# BLACKPEARLROBOT.net
KiCad netlist of a schematic drawn in Altium Designer
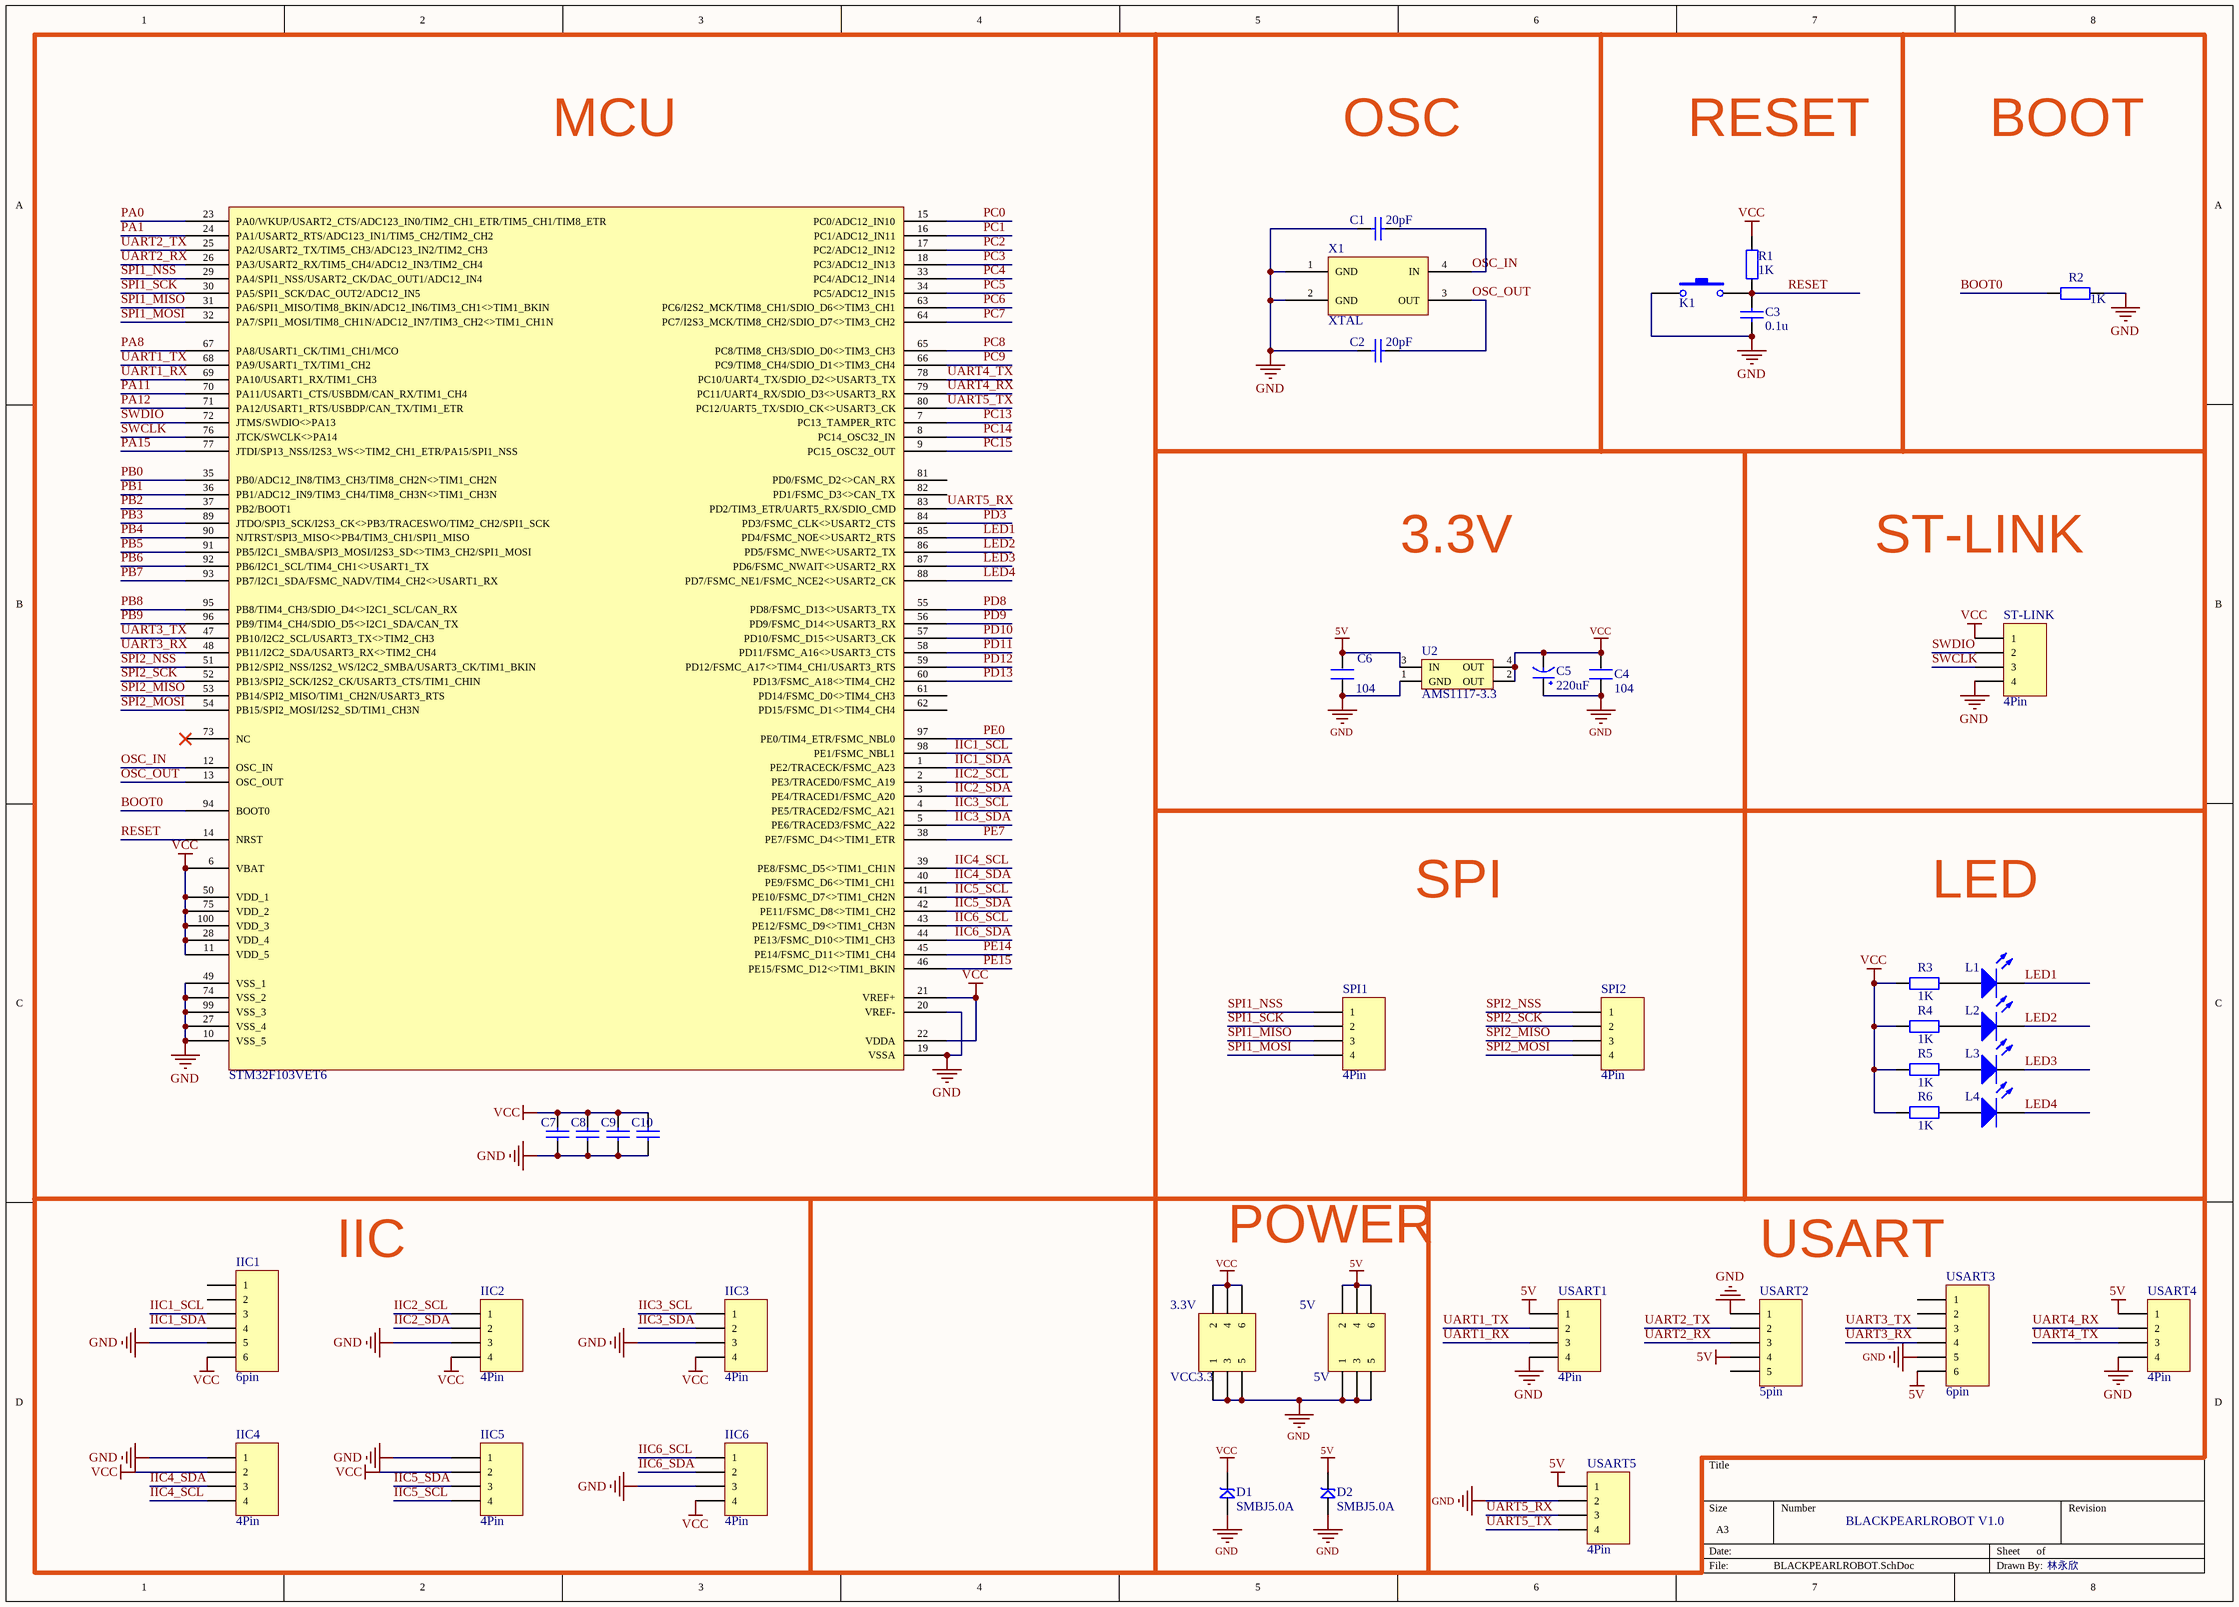
[diagram p0: BLACKPEARLROBOT.SchDoc]

(export (version "E")
  (design (tool "Eeschema 10.0.6"))
  (components
    (comp (ref "3.3V")
      (value "VCC3.3")
      (footprint "HDR2X3")
      (description "Header, 3-Pin, Dual row")
      (fields (field (name "PUBLISHER") "Altium Limited"))
      (libsource (lib "Explorer STM32F407封装库") (part "Header 3X2"))
    )
    (comp (ref "5V")
      (value "5V")
      (footprint "HDR2X3")
      (description "Header, 3-Pin, Dual row")
      (fields (field (name "PUBLISHER") "Altium Limited"))
      (libsource (lib "Explorer STM32F407封装库") (part "Header 3X2"))
    )
    (comp (ref "C1") (value "20pF") (footprint "Cap-0603") (libsource (lib "元件2") (part "Cap-0603")))
    (comp (ref "C2") (value "20pF") (footprint "Cap-0603") (libsource (lib "元件2") (part "Cap-0603")))
    (comp (ref "C3") (value "0.1u") (footprint "Cap-0603") (libsource (lib "元件2") (part "Cap-0603")))
    (comp (ref "C4") (value "104") (footprint "0603P") (libsource (lib "Explorer STM32F407封装库") (part "C")))
    (comp (ref "C5")
      (value "220uF")
      (footprint "CC6.56.5")
      (libsource (lib "Explorer STM32F407封装库") (part "CAP"))
    )
    (comp (ref "C6") (value "104") (footprint "0603P") (libsource (lib "Explorer STM32F407封装库") (part "C")))
    (comp (ref "C7") (value "0.1u") (footprint "Cap-0603") (libsource (lib "元件2") (part "Cap-0603")))
    (comp (ref "C8") (value "0.1u") (footprint "Cap-0603") (libsource (lib "元件2") (part "Cap-0603")))
    (comp (ref "C9") (value "0.1u") (footprint "Cap-0603") (libsource (lib "元件2") (part "Cap-0603")))
    (comp (ref "C10") (value "0.1u") (footprint "Cap-0603") (libsource (lib "元件2") (part "Cap-0603")))
    (comp (ref "D1")
      (value "SMBJ5.0A")
      (footprint "SMBJ")
      (description "TVS")
      (libsource (lib "Explorer STM32F407封装库") (part "SMBJ"))
    )
    (comp (ref "D2")
      (value "SMBJ5.0A")
      (footprint "SMBJ")
      (description "TVS")
      (libsource (lib "Explorer STM32F407封装库") (part "SMBJ"))
    )
    (comp (ref "IIC1")
      (value "6pin")
      (footprint "HDR1X6")
      (description "Header, 6-Pin")
      (fields (field (name "PUBLISHER") "Altium Limited"))
      (libsource (lib "Miscellaneous Connectors") (part "Header 6"))
    )
    (comp (ref "IIC2") (value "4Pin") (footprint "4Pin") (libsource (lib "元件2") (part "4Pin")))
    (comp (ref "IIC3") (value "4Pin") (footprint "4Pin") (libsource (lib "元件2") (part "4Pin")))
    (comp (ref "IIC4") (value "4Pin") (footprint "4Pin") (libsource (lib "元件2") (part "4Pin")))
    (comp (ref "IIC5") (value "4Pin") (footprint "4Pin") (libsource (lib "元件2") (part "4Pin")))
    (comp (ref "IIC6") (value "4Pin") (footprint "4Pin") (libsource (lib "元件2") (part "4Pin")))
    (comp (ref "K1") (value "KEY") (footprint "KEY-tie") (libsource (lib "元件2") (part "KEY-tie")))
    (comp (ref "L1") (value "LED-0805") (footprint "LED-0805") (libsource (lib "元件2") (part "LED-0805")))
    (comp (ref "L2") (value "LED-0805") (footprint "LED-0805") (libsource (lib "元件2") (part "LED-0805")))
    (comp (ref "L3") (value "LED-0805") (footprint "LED-0805") (libsource (lib "元件2") (part "LED-0805")))
    (comp (ref "L4") (value "LED-0805") (footprint "LED-0805") (libsource (lib "元件2") (part "LED-0805")))
    (comp (ref "R1") (value "1K") (footprint "RES-0603") (libsource (lib "元件2") (part "RST-0603")))
    (comp (ref "R2") (value "1K") (footprint "RES-0603") (libsource (lib "") (part "RST-0603_1")))
    (comp (ref "R3") (value "1K") (footprint "RES-0603") (libsource (lib "") (part "RST-0603_1")))
    (comp (ref "R4") (value "1K") (footprint "RES-0603") (libsource (lib "") (part "RST-0603_1")))
    (comp (ref "R5") (value "1K") (footprint "RES-0603") (libsource (lib "") (part "RST-0603_1")))
    (comp (ref "R6") (value "1K") (footprint "RES-0603") (libsource (lib "") (part "RST-0603_1")))
    (comp (ref "SPI1") (value "4Pin") (footprint "4Pin") (libsource (lib "元件2") (part "4Pin")))
    (comp (ref "SPI2") (value "4Pin") (footprint "4Pin") (libsource (lib "元件2") (part "4Pin")))
    (comp (ref "ST-LINK") (value "4Pin") (footprint "4Pin") (libsource (lib "元件2") (part "4Pin")))
    (comp (ref "U1")
      (value "STM32F103VET6")
      (footprint "STM32F103VET6")
      (libsource (lib "元件2") (part "STM32F103VET6"))
    )
    (comp (ref "U2")
      (value "AMS1117-3.3")
      (footprint "AMS1117")
      (libsource (lib "Explorer STM32F407封装库") (part "AMS1117"))
    )
    (comp (ref "USART1") (value "4Pin") (footprint "4Pin") (libsource (lib "元件2") (part "4Pin")))
    (comp (ref "USART2")
      (value "5pin")
      (footprint "HDR1X5")
      (description "Header, 5-Pin")
      (fields (field (name "PUBLISHER") "Altium Limited"))
      (libsource (lib "Miscellaneous Connectors") (part "Header 5"))
    )
    (comp (ref "USART3")
      (value "6pin")
      (footprint "HDR1X6")
      (description "Header, 6-Pin")
      (fields (field (name "PUBLISHER") "Altium Limited"))
      (libsource (lib "Miscellaneous Connectors") (part "Header 6"))
    )
    (comp (ref "USART4") (value "4Pin") (footprint "4Pin") (libsource (lib "元件2") (part "4Pin")))
    (comp (ref "USART5") (value "4Pin") (footprint "4Pin") (libsource (lib "元件2") (part "4Pin")))
    (comp (ref "X1") (value "XTAL") (footprint "XTAL-tie") (libsource (lib "元件2") (part "XTAL-tie")))
  )
  (nets
    (net (code "1") (name "/BOOT0") (class "Default")
      (node (ref "R2") (pin "1") (pinfunction "1_1") (pintype "passive"))
      (node (ref "U1") (pin "94") (pinfunction "BOOT0_94") (pintype "passive"))
    )
    (net (code "2") (name "/IIC1_SCL") (class "Default")
      (node (ref "IIC1") (pin "3") (pinfunction "3_3") (pintype "passive"))
      (node (ref "U1") (pin "98") (pinfunction "PE1/FSMC_NBL1_98") (pintype "passive"))
    )
    (net (code "3") (name "/IIC1_SDA") (class "Default")
      (node (ref "IIC1") (pin "4") (pinfunction "4_4") (pintype "passive"))
      (node (ref "U1") (pin "1") (pinfunction "PE2/TRACECK/FSMC_A23_1") (pintype "passive"))
    )
    (net (code "4") (name "/IIC2_SCL") (class "Default")
      (node (ref "IIC2") (pin "1") (pinfunction "1_1") (pintype "passive"))
      (node (ref "U1") (pin "2") (pinfunction "PE3/TRACED0/FSMC_A19_2") (pintype "passive"))
    )
    (net (code "5") (name "/IIC2_SDA") (class "Default")
      (node (ref "IIC2") (pin "2") (pinfunction "2_2") (pintype "passive"))
      (node (ref "U1") (pin "3") (pinfunction "PE4/TRACED1/FSMC_A20_3") (pintype "passive"))
    )
    (net (code "6") (name "/IIC3_SCL") (class "Default")
      (node (ref "IIC3") (pin "1") (pinfunction "1_1") (pintype "passive"))
      (node (ref "U1") (pin "4") (pinfunction "PE5/TRACED2/FSMC_A21_4") (pintype "passive"))
    )
    (net (code "7") (name "/IIC3_SDA") (class "Default")
      (node (ref "IIC3") (pin "2") (pinfunction "2_2") (pintype "passive"))
      (node (ref "U1") (pin "5") (pinfunction "PE6/TRACED3/FSMC_A22_5") (pintype "passive"))
    )
    (net (code "8") (name "/IIC4_SCL") (class "Default")
      (node (ref "IIC4") (pin "4") (pinfunction "4_4") (pintype "passive"))
      (node (ref "U1") (pin "39") (pinfunction "PE8/FSMC_D5<>TIM1_CH1N_39") (pintype "passive"))
    )
    (net (code "9") (name "/IIC4_SDA") (class "Default")
      (node (ref "IIC4") (pin "3") (pinfunction "3_3") (pintype "passive"))
      (node (ref "U1") (pin "40") (pinfunction "PE9/FSMC_D6<>TIM1_CH1_40") (pintype "passive"))
    )
    (net (code "10") (name "/IIC5_SCL") (class "Default")
      (node (ref "IIC5") (pin "4") (pinfunction "4_4") (pintype "passive"))
      (node (ref "U1") (pin "41") (pinfunction "PE10/FSMC_D7<>TIM1_CH2N_41") (pintype "passive"))
    )
    (net (code "11") (name "/IIC5_SDA") (class "Default")
      (node (ref "IIC5") (pin "3") (pinfunction "3_3") (pintype "passive"))
      (node (ref "U1") (pin "42") (pinfunction "PE11/FSMC_D8<>TIM1_CH2_42") (pintype "passive"))
    )
    (net (code "12") (name "/IIC6_SCL") (class "Default")
      (node (ref "IIC6") (pin "1") (pinfunction "1_1") (pintype "passive"))
      (node (ref "U1") (pin "43") (pinfunction "PE12/FSMC_D9<>TIM1_CH3N_43") (pintype "passive"))
    )
    (net (code "13") (name "/IIC6_SDA") (class "Default")
      (node (ref "IIC6") (pin "2") (pinfunction "2_2") (pintype "passive"))
      (node (ref "U1") (pin "44") (pinfunction "PE13/FSMC_D10<>TIM1_CH3_44") (pintype "passive"))
    )
    (net (code "14") (name "/LED1") (class "Default")
      (node (ref "L1") (pin "2") (pinfunction "K_2") (pintype "passive"))
      (node (ref "U1") (pin "85") (pinfunction "PD4/FSMC_NOE<>USART2_RTS_85") (pintype "passive"))
    )
    (net (code "15") (name "/LED2") (class "Default")
      (node (ref "L2") (pin "2") (pinfunction "K_2") (pintype "passive"))
      (node (ref "U1") (pin "86") (pinfunction "PD5/FSMC_NWE<>USART2_TX_86") (pintype "passive"))
    )
    (net (code "16") (name "/LED3") (class "Default")
      (node (ref "L3") (pin "2") (pinfunction "K_2") (pintype "passive"))
      (node (ref "U1") (pin "87") (pinfunction "PD6/FSMC_NWAIT<>USART2_RX_87") (pintype "passive"))
    )
    (net (code "17") (name "/LED4") (class "Default")
      (node (ref "L4") (pin "2") (pinfunction "K_2") (pintype "passive"))
      (node (ref "U1") (pin "88") (pinfunction "PD7/FSMC_NE1/FSMC_NCE2<>USART2_CK_88") (pintype "passive"))
    )
    (net (code "18") (name "/OSC_IN") (class "Default")
      (node (ref "C1") (pin "2") (pinfunction "2_2") (pintype "passive"))
      (node (ref "U1") (pin "12") (pinfunction "OSC_IN_12") (pintype "passive"))
      (node (ref "X1") (pin "4") (pinfunction "IN_4") (pintype "passive"))
    )
    (net (code "19") (name "/OSC_OUT") (class "Default")
      (node (ref "C2") (pin "2") (pinfunction "2_2") (pintype "passive"))
      (node (ref "U1") (pin "13") (pinfunction "OSC_OUT_13") (pintype "passive"))
      (node (ref "X1") (pin "3") (pinfunction "OUT_3") (pintype "passive"))
    )
    (net (code "20") (name "/PA0") (class "Default")
      (node (ref "U1") (pin "23") (pinfunction "PA0/WKUP/USART2_CTS/ADC123_IN0/TIM2_CH1_ETR/TIM5_CH1/TIM8_ETR_23") (pintype "passive"))
    )
    (net (code "21") (name "/PA1") (class "Default")
      (node (ref "U1") (pin "24") (pinfunction "PA1/USART2_RTS/ADC123_IN1/TIM5_CH2/TIM2_CH2_24") (pintype "passive"))
    )
    (net (code "22") (name "/PA8") (class "Default")
      (node (ref "U1") (pin "67") (pinfunction "PA8/USART1_CK/TIM1_CH1/MCO_67") (pintype "passive"))
    )
    (net (code "23") (name "/PA11") (class "Default")
      (node (ref "U1") (pin "70") (pinfunction "PA11/USART1_CTS/USBDM/CAN_RX/TIM1_CH4_70") (pintype "passive"))
    )
    (net (code "24") (name "/PA12") (class "Default")
      (node (ref "U1") (pin "71") (pinfunction "PA12/USART1_RTS/USBDP/CAN_TX/TIM1_ETR_71") (pintype "passive"))
    )
    (net (code "25") (name "/PA15") (class "Default")
      (node (ref "U1") (pin "77") (pinfunction "JTDI/SP13_NSS/I2S3_WS<>TIM2_CH1_ETR/PA15/SPI1_NSS_77") (pintype "passive"))
    )
    (net (code "26") (name "/PB0") (class "Default")
      (node (ref "U1") (pin "35") (pinfunction "PB0/ADC12_IN8/TIM3_CH3/TIM8_CH2N<>TIM1_CH2N_35") (pintype "passive"))
    )
    (net (code "27") (name "/PB1") (class "Default")
      (node (ref "U1") (pin "36") (pinfunction "PB1/ADC12_IN9/TIM3_CH4/TIM8_CH3N<>TIM1_CH3N_36") (pintype "passive"))
    )
    (net (code "28") (name "/PB2") (class "Default")
      (node (ref "U1") (pin "37") (pinfunction "PB2/BOOT1_37") (pintype "passive"))
    )
    (net (code "29") (name "/PB3") (class "Default")
      (node (ref "U1") (pin "89") (pinfunction "JTDO/SPI3_SCK/I2S3_CK<>PB3/TRACESWO/TIM2_CH2/SPI1_SCK_89") (pintype "passive"))
    )
    (net (code "30") (name "/PB4") (class "Default")
      (node (ref "U1") (pin "90") (pinfunction "NJTRST/SPI3_MISO<>PB4/TIM3_CH1/SPI1_MISO_90") (pintype "passive"))
    )
    (net (code "31") (name "/PB5") (class "Default")
      (node (ref "U1") (pin "91") (pinfunction "PB5/I2C1_SMBA/SPI3_MOSI/I2S3_SD<>TIM3_CH2/SPI1_MOSI_91") (pintype "passive"))
    )
    (net (code "32") (name "/PB6") (class "Default")
      (node (ref "U1") (pin "92") (pinfunction "PB6/I2C1_SCL/TIM4_CH1<>USART1_TX_92") (pintype "passive"))
    )
    (net (code "33") (name "/PB7") (class "Default")
      (node (ref "U1") (pin "93") (pinfunction "PB7/I2C1_SDA/FSMC_NADV/TIM4_CH2<>USART1_RX_93") (pintype "passive"))
    )
    (net (code "34") (name "/PB8") (class "Default")
      (node (ref "U1") (pin "95") (pinfunction "PB8/TIM4_CH3/SDIO_D4<>I2C1_SCL/CAN_RX_95") (pintype "passive"))
    )
    (net (code "35") (name "/PB9") (class "Default")
      (node (ref "U1") (pin "96") (pinfunction "PB9/TIM4_CH4/SDIO_D5<>I2C1_SDA/CAN_TX_96") (pintype "passive"))
    )
    (net (code "36") (name "/PC0") (class "Default")
      (node (ref "U1") (pin "15") (pinfunction "PC0/ADC12_IN10_15") (pintype "passive"))
    )
    (net (code "37") (name "/PC1") (class "Default")
      (node (ref "U1") (pin "16") (pinfunction "PC1/ADC12_IN11_16") (pintype "passive"))
    )
    (net (code "38") (name "/PC2") (class "Default")
      (node (ref "U1") (pin "17") (pinfunction "PC2/ADC12_IN12_17") (pintype "passive"))
    )
    (net (code "39") (name "/PC3") (class "Default")
      (node (ref "U1") (pin "18") (pinfunction "PC3/ADC12_IN13_18") (pintype "passive"))
    )
    (net (code "40") (name "/PC4") (class "Default")
      (node (ref "U1") (pin "33") (pinfunction "PC4/ADC12_IN14_33") (pintype "passive"))
    )
    (net (code "41") (name "/PC5") (class "Default")
      (node (ref "U1") (pin "34") (pinfunction "PC5/ADC12_IN15_34") (pintype "passive"))
    )
    (net (code "42") (name "/PC6") (class "Default")
      (node (ref "U1") (pin "63") (pinfunction "PC6/I2S2_MCK/TIM8_CH1/SDIO_D6<>TIM3_CH1_63") (pintype "passive"))
    )
    (net (code "43") (name "/PC7") (class "Default")
      (node (ref "U1") (pin "64") (pinfunction "PC7/I2S3_MCK/TIM8_CH2/SDIO_D7<>TIM3_CH2_64") (pintype "passive"))
    )
    (net (code "44") (name "/PC8") (class "Default")
      (node (ref "U1") (pin "65") (pinfunction "PC8/TIM8_CH3/SDIO_D0<>TIM3_CH3_65") (pintype "passive"))
    )
    (net (code "45") (name "/PC9") (class "Default")
      (node (ref "U1") (pin "66") (pinfunction "PC9/TIM8_CH4/SDIO_D1<>TIM3_CH4_66") (pintype "passive"))
    )
    (net (code "46") (name "/PC13") (class "Default")
      (node (ref "U1") (pin "7") (pinfunction "PC13_TAMPER_RTC_7") (pintype "passive"))
    )
    (net (code "47") (name "/PC14") (class "Default")
      (node (ref "U1") (pin "8") (pinfunction "PC14_OSC32_IN_8") (pintype "passive"))
    )
    (net (code "48") (name "/PC15") (class "Default")
      (node (ref "U1") (pin "9") (pinfunction "PC15_OSC32_OUT_9") (pintype "passive"))
    )
    (net (code "49") (name "/PD3") (class "Default")
      (node (ref "U1") (pin "84") (pinfunction "PD3/FSMC_CLK<>USART2_CTS_84") (pintype "passive"))
    )
    (net (code "50") (name "/PD8") (class "Default")
      (node (ref "U1") (pin "55") (pinfunction "PD8/FSMC_D13<>USART3_TX_55") (pintype "passive"))
    )
    (net (code "51") (name "/PD9") (class "Default")
      (node (ref "U1") (pin "56") (pinfunction "PD9/FSMC_D14<>USART3_RX_56") (pintype "passive"))
    )
    (net (code "52") (name "/PD10") (class "Default")
      (node (ref "U1") (pin "57") (pinfunction "PD10/FSMC_D15<>USART3_CK_57") (pintype "passive"))
    )
    (net (code "53") (name "/PD11") (class "Default")
      (node (ref "U1") (pin "58") (pinfunction "PD11/FSMC_A16<>USART3_CTS_58") (pintype "passive"))
    )
    (net (code "54") (name "/PD12") (class "Default")
      (node (ref "U1") (pin "59") (pinfunction "PD12/FSMC_A17<>TIM4_CH1/USART3_RTS_59") (pintype "passive"))
    )
    (net (code "55") (name "/PD13") (class "Default")
      (node (ref "U1") (pin "60") (pinfunction "PD13/FSMC_A18<>TIM4_CH2_60") (pintype "passive"))
    )
    (net (code "56") (name "/PE0") (class "Default")
      (node (ref "U1") (pin "97") (pinfunction "PE0/TIM4_ETR/FSMC_NBL0_97") (pintype "passive"))
    )
    (net (code "57") (name "/PE7") (class "Default")
      (node (ref "U1") (pin "38") (pinfunction "PE7/FSMC_D4<>TIM1_ETR_38") (pintype "passive"))
    )
    (net (code "58") (name "/PE14") (class "Default")
      (node (ref "U1") (pin "45") (pinfunction "PE14/FSMC_D11<>TIM1_CH4_45") (pintype "passive"))
    )
    (net (code "59") (name "/PE15") (class "Default")
      (node (ref "U1") (pin "46") (pinfunction "PE15/FSMC_D12<>TIM1_BKIN_46") (pintype "passive"))
    )
    (net (code "60") (name "/RESET") (class "Default")
      (node (ref "C3") (pin "2") (pinfunction "2_2") (pintype "passive"))
      (node (ref "K1") (pin "1") (pinfunction "1_1") (pintype "passive"))
      (node (ref "R1") (pin "1") (pinfunction "1_1") (pintype "passive"))
      (node (ref "U1") (pin "14") (pinfunction "NRST_14") (pintype "passive"))
    )
    (net (code "61") (name "/SPI1_MISO") (class "Default")
      (node (ref "SPI1") (pin "3") (pinfunction "3_3") (pintype "passive"))
      (node (ref "U1") (pin "31") (pinfunction "PA6/SPI1_MISO/TIM8_BKIN/ADC12_IN6/TIM3_CH1<>TIM1_BKIN_31") (pintype "passive"))
    )
    (net (code "62") (name "/SPI1_MOSI") (class "Default")
      (node (ref "SPI1") (pin "4") (pinfunction "4_4") (pintype "passive"))
      (node (ref "U1") (pin "32") (pinfunction "PA7/SPI1_MOSI/TIM8_CH1N/ADC12_IN7/TIM3_CH2<>TIM1_CH1N_32") (pintype "passive"))
    )
    (net (code "63") (name "/SPI1_NSS") (class "Default")
      (node (ref "SPI1") (pin "1") (pinfunction "1_1") (pintype "passive"))
      (node (ref "U1") (pin "29") (pinfunction "PA4/SPI1_NSS/USART2_CK/DAC_OUT1/ADC12_IN4_29") (pintype "passive"))
    )
    (net (code "64") (name "/SPI1_SCK") (class "Default")
      (node (ref "SPI1") (pin "2") (pinfunction "2_2") (pintype "passive"))
      (node (ref "U1") (pin "30") (pinfunction "PA5/SPI1_SCK/DAC_OUT2/ADC12_IN5_30") (pintype "passive"))
    )
    (net (code "65") (name "/SPI2_MISO") (class "Default")
      (node (ref "SPI2") (pin "3") (pinfunction "3_3") (pintype "passive"))
      (node (ref "U1") (pin "53") (pinfunction "PB14/SPI2_MISO/TIM1_CH2N/USART3_RTS_53") (pintype "passive"))
    )
    (net (code "66") (name "/SPI2_MOSI") (class "Default")
      (node (ref "SPI2") (pin "4") (pinfunction "4_4") (pintype "passive"))
      (node (ref "U1") (pin "54") (pinfunction "PB15/SPI2_MOSI/I2S2_SD/TIM1_CH3N_54") (pintype "passive"))
    )
    (net (code "67") (name "/SPI2_NSS") (class "Default")
      (node (ref "SPI2") (pin "1") (pinfunction "1_1") (pintype "passive"))
      (node (ref "U1") (pin "51") (pinfunction "PB12/SPI2_NSS/I2S2_WS/I2C2_SMBA/USART3_CK/TIM1_BKIN_51") (pintype "passive"))
    )
    (net (code "68") (name "/SPI2_SCK") (class "Default")
      (node (ref "SPI2") (pin "2") (pinfunction "2_2") (pintype "passive"))
      (node (ref "U1") (pin "52") (pinfunction "PB13/SPI2_SCK/I2S2_CK/USART3_CTS/TIM1_CHIN_52") (pintype "passive"))
    )
    (net (code "69") (name "/SWCLK") (class "Default")
      (node (ref "ST-LINK") (pin "3") (pinfunction "3_3") (pintype "passive"))
      (node (ref "U1") (pin "76") (pinfunction "JTCK/SWCLK<>PA14_76") (pintype "passive"))
    )
    (net (code "70") (name "/SWDIO") (class "Default")
      (node (ref "ST-LINK") (pin "2") (pinfunction "2_2") (pintype "passive"))
      (node (ref "U1") (pin "72") (pinfunction "JTMS/SWDIO<>PA13_72") (pintype "passive"))
    )
    (net (code "71") (name "/UART1_RX") (class "Default")
      (node (ref "U1") (pin "69") (pinfunction "PA10/USART1_RX/TIM1_CH3_69") (pintype "passive"))
      (node (ref "USART1") (pin "3") (pinfunction "3_3") (pintype "passive"))
    )
    (net (code "72") (name "/UART1_TX") (class "Default")
      (node (ref "U1") (pin "68") (pinfunction "PA9/USART1_TX/TIM1_CH2_68") (pintype "passive"))
      (node (ref "USART1") (pin "2") (pinfunction "2_2") (pintype "passive"))
    )
    (net (code "73") (name "/UART2_RX") (class "Default")
      (node (ref "U1") (pin "26") (pinfunction "PA3/USART2_RX/TIM5_CH4/ADC12_IN3/TIM2_CH4_26") (pintype "passive"))
      (node (ref "USART2") (pin "3") (pinfunction "3_3") (pintype "passive"))
    )
    (net (code "74") (name "/UART2_TX") (class "Default")
      (node (ref "U1") (pin "25") (pinfunction "PA2/USART2_TX/TIM5_CH3/ADC123_IN2/TIM2_CH3_25") (pintype "passive"))
      (node (ref "USART2") (pin "2") (pinfunction "2_2") (pintype "passive"))
    )
    (net (code "75") (name "/UART3_RX") (class "Default")
      (node (ref "U1") (pin "48") (pinfunction "PB11/I2C2_SDA/USART3_RX<>TIM2_CH4_48") (pintype "passive"))
      (node (ref "USART3") (pin "4") (pinfunction "4_4") (pintype "passive"))
    )
    (net (code "76") (name "/UART3_TX") (class "Default")
      (node (ref "U1") (pin "47") (pinfunction "PB10/I2C2_SCL/USART3_TX<>TIM2_CH3_47") (pintype "passive"))
      (node (ref "USART3") (pin "3") (pinfunction "3_3") (pintype "passive"))
    )
    (net (code "77") (name "/UART4_RX") (class "Default")
      (node (ref "U1") (pin "79") (pinfunction "PC11/UART4_RX/SDIO_D3<>USART3_RX_79") (pintype "passive"))
      (node (ref "USART4") (pin "2") (pinfunction "2_2") (pintype "passive"))
    )
    (net (code "78") (name "/UART4_TX") (class "Default")
      (node (ref "U1") (pin "78") (pinfunction "PC10/UART4_TX/SDIO_D2<>USART3_TX_78") (pintype "passive"))
      (node (ref "USART4") (pin "3") (pinfunction "3_3") (pintype "passive"))
    )
    (net (code "79") (name "/UART5_RX") (class "Default")
      (node (ref "U1") (pin "83") (pinfunction "PD2/TIM3_ETR/UART5_RX/SDIO_CMD_83") (pintype "passive"))
      (node (ref "USART5") (pin "3") (pinfunction "3_3") (pintype "passive"))
    )
    (net (code "80") (name "/UART5_TX") (class "Default")
      (node (ref "U1") (pin "80") (pinfunction "PC12/UART5_TX/SDIO_CK<>USART3_CK_80") (pintype "passive"))
      (node (ref "USART5") (pin "4") (pinfunction "4_4") (pintype "passive"))
    )
    (net (code "81") (name "5V") (class "Default")
      (node (ref "5V") (pin "2") (pinfunction "2_2") (pintype "passive"))
      (node (ref "5V") (pin "4") (pinfunction "4_4") (pintype "passive"))
      (node (ref "5V") (pin "6") (pinfunction "6_6") (pintype "passive"))
      (node (ref "C6") (pin "2") (pintype "passive"))
      (node (ref "D2") (pin "2") (pintype "passive"))
      (node (ref "U2") (pin "3") (pinfunction "IN_3") (pintype "passive"))
      (node (ref "USART1") (pin "1") (pinfunction "1_1") (pintype "passive"))
      (node (ref "USART2") (pin "4") (pinfunction "4_4") (pintype "passive"))
      (node (ref "USART3") (pin "6") (pinfunction "6_6") (pintype "passive"))
      (node (ref "USART4") (pin "1") (pinfunction "1_1") (pintype "passive"))
      (node (ref "USART5") (pin "1") (pinfunction "1_1") (pintype "passive"))
    )
    (net (code "82") (name "GND") (class "Default")
      (node (ref "3.3V") (pin "1") (pinfunction "1_1") (pintype "passive"))
      (node (ref "3.3V") (pin "3") (pinfunction "3_3") (pintype "passive"))
      (node (ref "3.3V") (pin "5") (pinfunction "5_5") (pintype "passive"))
      (node (ref "5V") (pin "1") (pinfunction "1_1") (pintype "passive"))
      (node (ref "5V") (pin "3") (pinfunction "3_3") (pintype "passive"))
      (node (ref "5V") (pin "5") (pinfunction "5_5") (pintype "passive"))
      (node (ref "C1") (pin "1") (pinfunction "1_1") (pintype "passive"))
      (node (ref "C10") (pin "1") (pinfunction "1_1") (pintype "passive"))
      (node (ref "C2") (pin "1") (pinfunction "1_1") (pintype "passive"))
      (node (ref "C3") (pin "1") (pinfunction "1_1") (pintype "passive"))
      (node (ref "C4") (pin "2") (pintype "passive"))
      (node (ref "C5") (pin "1") (pinfunction "VCC_1") (pintype "passive"))
      (node (ref "C6") (pin "1") (pintype "passive"))
      (node (ref "C7") (pin "1") (pinfunction "1_1") (pintype "passive"))
      (node (ref "C8") (pin "1") (pinfunction "1_1") (pintype "passive"))
      (node (ref "C9") (pin "1") (pinfunction "1_1") (pintype "passive"))
      (node (ref "D1") (pin "1") (pintype "passive"))
      (node (ref "D2") (pin "1") (pintype "passive"))
      (node (ref "IIC1") (pin "5") (pinfunction "5_5") (pintype "passive"))
      (node (ref "IIC2") (pin "3") (pinfunction "3_3") (pintype "passive"))
      (node (ref "IIC3") (pin "3") (pinfunction "3_3") (pintype "passive"))
      (node (ref "IIC4") (pin "1") (pinfunction "1_1") (pintype "passive"))
      (node (ref "IIC5") (pin "1") (pinfunction "1_1") (pintype "passive"))
      (node (ref "IIC6") (pin "3") (pinfunction "3_3") (pintype "passive"))
      (node (ref "K1") (pin "2") (pinfunction "2_2") (pintype "passive"))
      (node (ref "R2") (pin "2") (pinfunction "2_2") (pintype "passive"))
      (node (ref "ST-LINK") (pin "4") (pinfunction "4_4") (pintype "passive"))
      (node (ref "U1") (pin "10") (pinfunction "VSS_5_10") (pintype "passive"))
      (node (ref "U1") (pin "19") (pinfunction "VSSA_19") (pintype "passive"))
      (node (ref "U1") (pin "20") (pinfunction "VREF-_20") (pintype "passive"))
      (node (ref "U1") (pin "27") (pinfunction "VSS_4_27") (pintype "passive"))
      (node (ref "U1") (pin "49") (pinfunction "VSS_1_49") (pintype "passive"))
      (node (ref "U1") (pin "74") (pinfunction "VSS_2_74") (pintype "passive"))
      (node (ref "U1") (pin "99") (pinfunction "VSS_3_99") (pintype "passive"))
      (node (ref "U2") (pin "1") (pinfunction "GND_1") (pintype "passive"))
      (node (ref "USART1") (pin "4") (pinfunction "4_4") (pintype "passive"))
      (node (ref "USART2") (pin "1") (pinfunction "1_1") (pintype "passive"))
      (node (ref "USART3") (pin "5") (pinfunction "5_5") (pintype "passive"))
      (node (ref "USART4") (pin "4") (pinfunction "4_4") (pintype "passive"))
      (node (ref "USART5") (pin "2") (pinfunction "2_2") (pintype "passive"))
      (node (ref "X1") (pin "1") (pinfunction "GND_1") (pintype "passive"))
      (node (ref "X1") (pin "2") (pinfunction "GND_2") (pintype "passive"))
    )
    (net (code "83") (name "Net-(L1-A)") (class "Default")
      (node (ref "L1") (pin "1") (pinfunction "A_1") (pintype "passive"))
      (node (ref "R3") (pin "2") (pinfunction "2_2") (pintype "passive"))
    )
    (net (code "84") (name "Net-(L2-A)") (class "Default")
      (node (ref "L2") (pin "1") (pinfunction "A_1") (pintype "passive"))
      (node (ref "R4") (pin "2") (pinfunction "2_2") (pintype "passive"))
    )
    (net (code "85") (name "Net-(L3-A)") (class "Default")
      (node (ref "L3") (pin "1") (pinfunction "A_1") (pintype "passive"))
      (node (ref "R5") (pin "2") (pinfunction "2_2") (pintype "passive"))
    )
    (net (code "86") (name "Net-(L4-A)") (class "Default")
      (node (ref "L4") (pin "1") (pinfunction "A_1") (pintype "passive"))
      (node (ref "R6") (pin "2") (pinfunction "2_2") (pintype "passive"))
    )
    (net (code "87") (name "VCC") (class "Default")
      (node (ref "3.3V") (pin "2") (pinfunction "2_2") (pintype "passive"))
      (node (ref "3.3V") (pin "4") (pinfunction "4_4") (pintype "passive"))
      (node (ref "3.3V") (pin "6") (pinfunction "6_6") (pintype "passive"))
      (node (ref "C10") (pin "2") (pinfunction "2_2") (pintype "passive"))
      (node (ref "C4") (pin "1") (pintype "passive"))
      (node (ref "C5") (pin "2") (pinfunction "GND_2") (pintype "passive"))
      (node (ref "C7") (pin "2") (pinfunction "2_2") (pintype "passive"))
      (node (ref "C8") (pin "2") (pinfunction "2_2") (pintype "passive"))
      (node (ref "C9") (pin "2") (pinfunction "2_2") (pintype "passive"))
      (node (ref "D1") (pin "2") (pintype "passive"))
      (node (ref "IIC1") (pin "6") (pinfunction "6_6") (pintype "passive"))
      (node (ref "IIC2") (pin "4") (pinfunction "4_4") (pintype "passive"))
      (node (ref "IIC3") (pin "4") (pinfunction "4_4") (pintype "passive"))
      (node (ref "IIC4") (pin "2") (pinfunction "2_2") (pintype "passive"))
      (node (ref "IIC5") (pin "2") (pinfunction "2_2") (pintype "passive"))
      (node (ref "IIC6") (pin "4") (pinfunction "4_4") (pintype "passive"))
      (node (ref "R1") (pin "2") (pinfunction "2_2") (pintype "passive"))
      (node (ref "R3") (pin "1") (pinfunction "1_1") (pintype "passive"))
      (node (ref "R4") (pin "1") (pinfunction "1_1") (pintype "passive"))
      (node (ref "R5") (pin "1") (pinfunction "1_1") (pintype "passive"))
      (node (ref "R6") (pin "1") (pinfunction "1_1") (pintype "passive"))
      (node (ref "ST-LINK") (pin "1") (pinfunction "1_1") (pintype "passive"))
      (node (ref "U1") (pin "100") (pinfunction "VDD_3_100") (pintype "passive"))
      (node (ref "U1") (pin "11") (pinfunction "VDD_5_11") (pintype "passive"))
      (node (ref "U1") (pin "21") (pinfunction "VREF+_21") (pintype "passive"))
      (node (ref "U1") (pin "22") (pinfunction "VDDA_22") (pintype "passive"))
      (node (ref "U1") (pin "28") (pinfunction "VDD_4_28") (pintype "passive"))
      (node (ref "U1") (pin "50") (pinfunction "VDD_1_50") (pintype "passive"))
      (node (ref "U1") (pin "6") (pinfunction "VBAT_6") (pintype "passive"))
      (node (ref "U1") (pin "75") (pinfunction "VDD_2_75") (pintype "passive"))
      (node (ref "U2") (pin "2") (pinfunction "OUT_2") (pintype "passive"))
      (node (ref "U2") (pin "4") (pinfunction "OUT_4") (pintype "passive"))
    )
    (net (code "88") (name "unconnected-(IIC1-Pad1)") (class "Default")
      (node (ref "IIC1") (pin "1") (pinfunction "1_1") (pintype "passive"))
    )
    (net (code "89") (name "unconnected-(IIC1-Pad2)") (class "Default")
      (node (ref "IIC1") (pin "2") (pinfunction "2_2") (pintype "passive"))
    )
    (net (code "90") (name "unconnected-(U1-NC-Pad73)") (class "Default")
      (node (ref "U1") (pin "73") (pinfunction "NC_73") (pintype "passive+no_connect"))
    )
    (net (code "91") (name "unconnected-(U1-PD0{slash}FSMC_D2<>CAN_RX-Pad81)") (class "Default")
      (node (ref "U1") (pin "81") (pinfunction "PD0/FSMC_D2<>CAN_RX_81") (pintype "passive"))
    )
    (net (code "92") (name "unconnected-(U1-PD1{slash}FSMC_D3<>CAN_TX-Pad82)") (class "Default")
      (node (ref "U1") (pin "82") (pinfunction "PD1/FSMC_D3<>CAN_TX_82") (pintype "passive"))
    )
    (net (code "93") (name "unconnected-(U1-PD14{slash}FSMC_D0<>TIM4_CH3-Pad61)") (class "Default")
      (node (ref "U1") (pin "61") (pinfunction "PD14/FSMC_D0<>TIM4_CH3_61") (pintype "passive"))
    )
    (net (code "94") (name "unconnected-(U1-PD15{slash}FSMC_D1<>TIM4_CH4-Pad62)") (class "Default")
      (node (ref "U1") (pin "62") (pinfunction "PD15/FSMC_D1<>TIM4_CH4_62") (pintype "passive"))
    )
    (net (code "95") (name "unconnected-(USART2-Pad5)") (class "Default")
      (node (ref "USART2") (pin "5") (pinfunction "5_5") (pintype "passive"))
    )
    (net (code "96") (name "unconnected-(USART3-Pad1)") (class "Default")
      (node (ref "USART3") (pin "1") (pinfunction "1_1") (pintype "passive"))
    )
    (net (code "97") (name "unconnected-(USART3-Pad2)") (class "Default")
      (node (ref "USART3") (pin "2") (pinfunction "2_2") (pintype "passive"))
    )
  )
)
